# epd_driver.net
KiCad netlist of a schematic drawn in Altium Designer
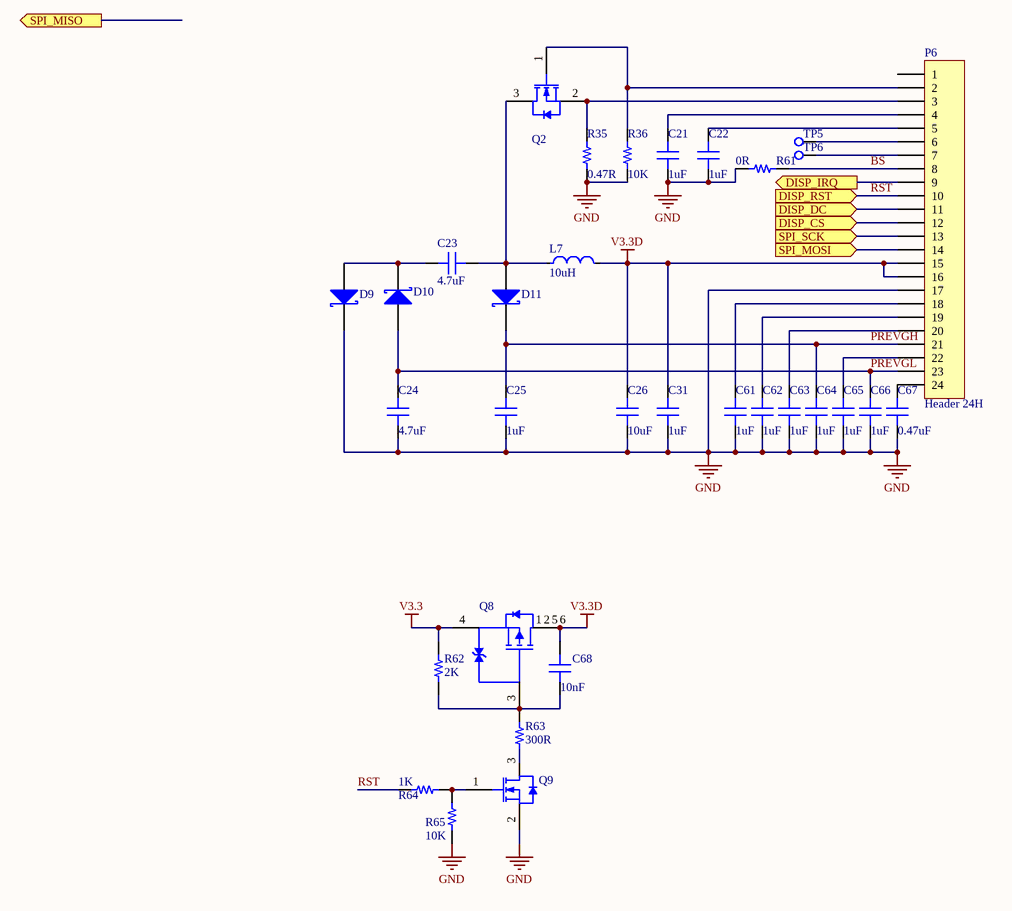
[diagram p0: epd_driver.SchDoc]

(export (version "E")
  (design (tool "Eeschema 10.0.6"))
  (components
    (comp (ref "C21")
      (value "1uF")
      (footprint "CAP 0603_1608")
      (description "SMT Capacitor")
      (fields (field (name "MF") "Murata") (field (name "MP") "GRT188R61H105KE13D"))
      (libsource (lib "Capacitor") (part "Capacitor"))
    )
    (comp (ref "C22")
      (value "1uF")
      (footprint "CAP 0603_1608")
      (description "SMT Capacitor")
      (fields (field (name "MF") "Murata") (field (name "MP") "GRT188R61H105KE13D"))
      (libsource (lib "Capacitor") (part "Capacitor"))
    )
    (comp (ref "C23")
      (value "4.7uF")
      (footprint "CAP 0603_1608")
      (description "SMT Capacitor")
      (fields (field (name "MF") "Murata") (field (name "MP") "GRM188C81E475KE11J"))
      (libsource (lib "Capacitor") (part "Capacitor"))
    )
    (comp (ref "C24")
      (value "4.7uF")
      (footprint "CAP 0603_1608")
      (description "SMT Capacitor")
      (fields (field (name "MF") "Murata") (field (name "MP") "GRM188C81E475KE11J"))
      (libsource (lib "Capacitor") (part "Capacitor"))
    )
    (comp (ref "C25")
      (value "1uF")
      (footprint "CAP 0603_1608")
      (description "SMT Capacitor")
      (fields (field (name "MF") "Murata") (field (name "MP") "GRT188R61H105KE13D"))
      (libsource (lib "Capacitor") (part "Capacitor"))
    )
    (comp (ref "C26")
      (value "10uF")
      (footprint "CAP 0603_1608")
      (description "SMT Capacitor")
      (fields (field (name "MF") "Murata") (field (name "MP") "GRM188R61C106MAALD"))
      (libsource (lib "Capacitor") (part "Capacitor"))
    )
    (comp (ref "C31")
      (value "1uF")
      (footprint "CAP 0603_1608")
      (description "SMT Capacitor")
      (fields (field (name "MF") "Murata") (field (name "MP") "GRT188R61H105KE13D"))
      (libsource (lib "Capacitor") (part "Capacitor"))
    )
    (comp (ref "C61")
      (value "1uF")
      (footprint "CAP 0603_1608")
      (description "SMT Capacitor")
      (fields (field (name "MF") "Murata") (field (name "MP") "GRT188R61H105KE13D"))
      (libsource (lib "Capacitor") (part "Capacitor"))
    )
    (comp (ref "C62")
      (value "1uF")
      (footprint "CAP 0603_1608")
      (description "SMT Capacitor")
      (fields (field (name "MF") "Murata") (field (name "MP") "GRT188R61H105KE13D"))
      (libsource (lib "Capacitor") (part "Capacitor"))
    )
    (comp (ref "C63")
      (value "1uF")
      (footprint "CAP 0603_1608")
      (description "SMT Capacitor")
      (fields (field (name "MF") "Murata") (field (name "MP") "GRT188R61H105KE13D"))
      (libsource (lib "Capacitor") (part "Capacitor"))
    )
    (comp (ref "C64")
      (value "1uF")
      (footprint "CAP 0603_1608")
      (description "SMT Capacitor")
      (fields (field (name "MF") "Murata") (field (name "MP") "GRT188R61H105KE13D"))
      (libsource (lib "Capacitor") (part "Capacitor"))
    )
    (comp (ref "C65")
      (value "1uF")
      (footprint "CAP 0603_1608")
      (description "SMT Capacitor")
      (fields (field (name "MF") "Murata") (field (name "MP") "GRT188R61H105KE13D"))
      (libsource (lib "Capacitor") (part "Capacitor"))
    )
    (comp (ref "C66")
      (value "1uF")
      (footprint "CAP 0603_1608")
      (description "SMT Capacitor")
      (fields (field (name "MF") "Murata") (field (name "MP") "GRT188R61H105KE13D"))
      (libsource (lib "Capacitor") (part "Capacitor"))
    )
    (comp (ref "C67")
      (value "0.47uF")
      (footprint "CAP 0603_1608")
      (description "SMT Capacitor")
      (fields (field (name "MF") "Samsung") (field (name "MP") "CL10B474KA8NFNC"))
      (libsource (lib "Capacitor") (part "Capacitor"))
    )
    (comp (ref "C68")
      (value "10nF")
      (footprint "CAP 0603_1608")
      (description "SMT Capacitor")
      (fields (field (name "MF") "Murata") (field (name "MP") "GRM1885C1E103JA01D"))
      (libsource (lib "Capacitor") (part "Capacitor"))
    )
    (comp (ref "D9")
      (value "*")
      (footprint "Rohm_TUMD2M_MFG")
      (fields (field (name "MF") "Toshiba") (field (name "MP") "CUHS20F30,H3F"))
      (libsource (lib "Diode") (part "Schottky Diode"))
    )
    (comp (ref "D10")
      (value "*")
      (footprint "Rohm_TUMD2M_MFG")
      (fields (field (name "MF") "Toshiba") (field (name "MP") "CUHS20F30,H3F"))
      (libsource (lib "Diode") (part "Schottky Diode"))
    )
    (comp (ref "D11")
      (value "*")
      (footprint "Rohm_TUMD2M_MFG")
      (fields (field (name "MF") "Toshiba") (field (name "MP") "CUHS20F30,H3F"))
      (libsource (lib "Diode") (part "Schottky Diode"))
    )
    (comp (ref "L7")
      (value "10uH")
      (footprint "IND 1008_2520")
      (description "Fixed Inductors 2.2uH 20% High Temp AEC-Q200")
      (fields (field (name "MF") "Murata") (field (name "MP") "DFE252012F-100M=P2"))
      (libsource (lib "Inductor") (part "Inductor_sm"))
    )
    (comp (ref "P6")
      (value "Header 24H")
      (footprint "Amphenol_FFC/FPC_24_0.5mm")
      (description "Header, 24-Pin, Right Angle")
      (fields
        (field (name "MF") "Amphenol")
        (field (name "MP") "10051922-2410EHLF")
        (field (name "PUBLISHER") "Altium Limited")
      )
      (libsource (lib "Connector") (part "Header 24H"))
    )
    (comp (ref "Q2")
      (value "N Mosfet")
      (footprint "ON SEMI SOT-23-3")
      (description "N-Channel Enhancement Mode MOS Transistor, 30 V, 0.85 A, 3-Pin SOT23, Tape and Reel")
      (fields (field (name "MF") "Diodes") (field (name "MP") "DMN2053U-7"))
      (libsource (lib "Mosfet") (part "Mosfet-N"))
    )
    (comp (ref "Q8")
      (value "P Mosfet")
      (footprint "Diodes_Inc._TSOT26_MFG")
      (description "P-Channel Enhancement Mode MOS Transistor, 3-Pin SOT23")
      (fields (field (name "MF") "Vishay") (field (name "MP") "SI3421DV-T1-GE3"))
      (libsource (lib "Mosfet") (part "Mosfet-P-6_ESD"))
    )
    (comp (ref "Q9")
      (value "N Mosfet")
      (footprint "ON SEMI SOT-23-3")
      (description "N-Channel Enhancement Mode MOS Transistor, 30 V, 0.85 A, 3-Pin SOT23, Tape and Reel")
      (fields (field (name "MF") "Diodes") (field (name "MP") "DMN2053U-7"))
      (libsource (lib "Mosfet") (part "Mosfet-N"))
    )
    (comp (ref "R35")
      (value "0.47R")
      (footprint "RES 0603_1608")
      (description "SMT Resistor")
      (fields (field (name "MF") "Panasonic") (field (name "MP") "ERJ-3RQFR47V"))
      (libsource (lib "Resistor") (part "Resistor"))
    )
    (comp (ref "R36")
      (value "10K")
      (footprint "RES 0603_1608")
      (description "SMT Resistor")
      (fields (field (name "MF") "YAGEO") (field (name "MP") "AC0603FR-0710KL"))
      (libsource (lib "Resistor") (part "Resistor"))
    )
    (comp (ref "R61")
      (value "0R")
      (footprint "RES 0603_1608")
      (description "SMT Resistor")
      (fields (field (name "MF") "YAGEO") (field (name "MP") "AC0603FR-070RL"))
      (libsource (lib "Resistor") (part "Resistor"))
    )
    (comp (ref "R62")
      (value "2K")
      (footprint "RES 0603_1608")
      (description "SMT Resistor")
      (fields (field (name "MF") "YAGEO") (field (name "MP") "AC0603FR-072KL"))
      (libsource (lib "Resistor") (part "Resistor"))
    )
    (comp (ref "R63")
      (value "300R")
      (footprint "RES 0603_1608")
      (description "SMT Resistor")
      (fields (field (name "MF") "YAGEO") (field (name "MP") "AC0603FR-07300RL"))
      (libsource (lib "Resistor") (part "Resistor"))
    )
    (comp (ref "R64")
      (value "1K")
      (footprint "RES 0603_1608")
      (description "SMT Resistor")
      (fields (field (name "MF") "YAGEO") (field (name "MP") "AC0603FR-071KL"))
      (libsource (lib "Resistor") (part "Resistor"))
    )
    (comp (ref "R65")
      (value "10K")
      (footprint "RES 0603_1608")
      (description "SMT Resistor")
      (fields (field (name "MF") "YAGEO") (field (name "MP") "AC0603FR-0710KL"))
      (libsource (lib "Resistor") (part "Resistor"))
    )
    (comp (ref "TP5")
      (value "Test Point")
      (footprint "TPSMD_S1")
      (libsource (lib "Passive") (part "Test Point"))
    )
    (comp (ref "TP6")
      (value "Test Point")
      (footprint "TPSMD_S1")
      (libsource (lib "Passive") (part "Test Point"))
    )
  )
  (nets
    (net (code "1") (name "/BS") (class "Default")
      (node (ref "P6") (pin "8") (pinfunction "8_8") (pintype "passive"))
      (node (ref "R61") (pin "1") (pinfunction "1_1") (pintype "passive"))
    )
    (net (code "2") (name "/DISP_CS") (class "Default")
      (node (ref "P6") (pin "12") (pinfunction "12_12") (pintype "passive"))
    )
    (net (code "3") (name "/DISP_DC") (class "Default")
      (node (ref "P6") (pin "11") (pinfunction "11_11") (pintype "passive"))
    )
    (net (code "4") (name "/DISP_IRQ") (class "Default")
      (node (ref "P6") (pin "9") (pinfunction "9_9") (pintype "passive"))
    )
    (net (code "5") (name "/PREVGH") (class "Default")
      (node (ref "C25") (pin "2") (pinfunction "2_2") (pintype "passive"))
      (node (ref "C64") (pin "2") (pinfunction "2_2") (pintype "passive"))
      (node (ref "D11") (pin "1") (pinfunction "K_1") (pintype "passive"))
      (node (ref "P6") (pin "21") (pinfunction "21_21") (pintype "passive"))
    )
    (net (code "6") (name "/PREVGL") (class "Default")
      (node (ref "C24") (pin "1") (pinfunction "1_1") (pintype "passive"))
      (node (ref "C66") (pin "2") (pinfunction "2_2") (pintype "passive"))
      (node (ref "D10") (pin "2") (pinfunction "A_2") (pintype "passive"))
      (node (ref "P6") (pin "23") (pinfunction "23_23") (pintype "passive"))
    )
    (net (code "7") (name "/RST") (class "Default")
      (node (ref "P6") (pin "10") (pinfunction "10_10") (pintype "passive"))
      (node (ref "R64") (pin "1") (pinfunction "1_1") (pintype "passive"))
    )
    (net (code "9") (name "/SPI_MOSI") (class "Default")
      (node (ref "P6") (pin "14") (pinfunction "14_14") (pintype "passive"))
    )
    (net (code "10") (name "/SPI_SCK") (class "Default")
      (node (ref "P6") (pin "13") (pinfunction "13_13") (pintype "passive"))
    )
    (net (code "11") (name "GND") (class "Default")
      (node (ref "C21") (pin "1") (pinfunction "1_1") (pintype "passive"))
      (node (ref "C22") (pin "1") (pinfunction "1_1") (pintype "passive"))
      (node (ref "C24") (pin "2") (pinfunction "2_2") (pintype "passive"))
      (node (ref "C25") (pin "1") (pinfunction "1_1") (pintype "passive"))
      (node (ref "C26") (pin "2") (pinfunction "2_2") (pintype "passive"))
      (node (ref "C31") (pin "1") (pinfunction "1_1") (pintype "passive"))
      (node (ref "C61") (pin "1") (pinfunction "1_1") (pintype "passive"))
      (node (ref "C62") (pin "1") (pinfunction "1_1") (pintype "passive"))
      (node (ref "C63") (pin "1") (pinfunction "1_1") (pintype "passive"))
      (node (ref "C64") (pin "1") (pinfunction "1_1") (pintype "passive"))
      (node (ref "C65") (pin "1") (pinfunction "1_1") (pintype "passive"))
      (node (ref "C66") (pin "1") (pinfunction "1_1") (pintype "passive"))
      (node (ref "C67") (pin "1") (pinfunction "1_1") (pintype "passive"))
      (node (ref "D9") (pin "1") (pinfunction "K_1") (pintype "passive"))
      (node (ref "P6") (pin "17") (pinfunction "17_17") (pintype "passive"))
      (node (ref "Q9") (pin "2") (pinfunction "S_2") (pintype "passive"))
      (node (ref "R35") (pin "1") (pinfunction "1_1") (pintype "passive"))
      (node (ref "R36") (pin "2") (pinfunction "2_2") (pintype "passive"))
      (node (ref "R61") (pin "2") (pinfunction "2_2") (pintype "passive"))
      (node (ref "R65") (pin "1") (pinfunction "1_1") (pintype "passive"))
    )
    (net (code "12") (name "Net-(C21-Pad2)") (class "Default")
      (node (ref "C21") (pin "2") (pinfunction "2_2") (pintype "passive"))
      (node (ref "P6") (pin "4") (pinfunction "4_4") (pintype "passive"))
    )
    (net (code "13") (name "Net-(C22-Pad2)") (class "Default")
      (node (ref "C22") (pin "2") (pinfunction "2_2") (pintype "passive"))
      (node (ref "P6") (pin "5") (pinfunction "5_5") (pintype "passive"))
    )
    (net (code "14") (name "Net-(C61-Pad2)") (class "Default")
      (node (ref "C61") (pin "2") (pinfunction "2_2") (pintype "passive"))
      (node (ref "P6") (pin "18") (pinfunction "18_18") (pintype "passive"))
    )
    (net (code "15") (name "Net-(C62-Pad2)") (class "Default")
      (node (ref "C62") (pin "2") (pinfunction "2_2") (pintype "passive"))
      (node (ref "P6") (pin "19") (pinfunction "19_19") (pintype "passive"))
    )
    (net (code "16") (name "Net-(C63-Pad2)") (class "Default")
      (node (ref "C63") (pin "2") (pinfunction "2_2") (pintype "passive"))
      (node (ref "P6") (pin "20") (pinfunction "20_20") (pintype "passive"))
    )
    (net (code "17") (name "Net-(C65-Pad2)") (class "Default")
      (node (ref "C65") (pin "2") (pinfunction "2_2") (pintype "passive"))
      (node (ref "P6") (pin "22") (pinfunction "22_22") (pintype "passive"))
    )
    (net (code "18") (name "Net-(C67-Pad2)") (class "Default")
      (node (ref "C67") (pin "2") (pinfunction "2_2") (pintype "passive"))
      (node (ref "P6") (pin "24") (pinfunction "24_24") (pintype "passive"))
    )
    (net (code "19") (name "Net-(D10-K)") (class "Default")
      (node (ref "C23") (pin "1") (pinfunction "1_1") (pintype "passive"))
      (node (ref "D10") (pin "1") (pinfunction "K_1") (pintype "passive"))
      (node (ref "D9") (pin "2") (pinfunction "A_2") (pintype "passive"))
    )
    (net (code "20") (name "Net-(D11-A)") (class "Default")
      (node (ref "C23") (pin "2") (pinfunction "2_2") (pintype "passive"))
      (node (ref "D11") (pin "2") (pinfunction "A_2") (pintype "passive"))
      (node (ref "L7") (pin "1") (pinfunction "1_1") (pintype "passive"))
      (node (ref "Q2") (pin "3") (pinfunction "D_3") (pintype "passive"))
    )
    (net (code "21") (name "Net-(Q2-G)") (class "Default")
      (node (ref "P6") (pin "2") (pinfunction "2_2") (pintype "passive"))
      (node (ref "Q2") (pin "1") (pinfunction "G_1") (pintype "passive"))
      (node (ref "R36") (pin "1") (pinfunction "1_1") (pintype "passive"))
    )
    (net (code "22") (name "Net-(Q2-S)") (class "Default")
      (node (ref "P6") (pin "3") (pinfunction "3_3") (pintype "passive"))
      (node (ref "Q2") (pin "2") (pinfunction "S_2") (pintype "passive"))
      (node (ref "R35") (pin "2") (pinfunction "2_2") (pintype "passive"))
    )
    (net (code "23") (name "Net-(Q8-G)") (class "Default")
      (node (ref "C68") (pin "2") (pinfunction "2_2") (pintype "passive"))
      (node (ref "Q8") (pin "3") (pinfunction "G_3") (pintype "passive"))
      (node (ref "R62") (pin "2") (pinfunction "2_2") (pintype "passive"))
      (node (ref "R63") (pin "2") (pinfunction "2_2") (pintype "passive"))
    )
    (net (code "24") (name "Net-(Q9-D)") (class "Default")
      (node (ref "Q9") (pin "3") (pinfunction "D_3") (pintype "passive"))
      (node (ref "R63") (pin "1") (pinfunction "1_1") (pintype "passive"))
    )
    (net (code "25") (name "Net-(Q9-G)") (class "Default")
      (node (ref "Q9") (pin "1") (pinfunction "G_1") (pintype "passive"))
      (node (ref "R64") (pin "2") (pinfunction "2_2") (pintype "passive"))
      (node (ref "R65") (pin "2") (pinfunction "2_2") (pintype "passive"))
    )
    (net (code "26") (name "Net-(TP5-TP)") (class "Default")
      (node (ref "P6") (pin "6") (pinfunction "6_6") (pintype "passive"))
      (node (ref "TP5") (pin "1") (pinfunction "TP_1") (pintype "passive"))
    )
    (net (code "27") (name "Net-(TP6-TP)") (class "Default")
      (node (ref "P6") (pin "7") (pinfunction "7_7") (pintype "passive"))
      (node (ref "TP6") (pin "1") (pinfunction "TP_1") (pintype "passive"))
    )
    (net (code "28") (name "V3.3") (class "Default")
      (node (ref "Q8") (pin "4") (pinfunction "S_4") (pintype "passive"))
      (node (ref "R62") (pin "1") (pinfunction "1_1") (pintype "passive"))
    )
    (net (code "29") (name "V3.3D") (class "Default")
      (node (ref "C26") (pin "1") (pinfunction "1_1") (pintype "passive"))
      (node (ref "C31") (pin "2") (pinfunction "2_2") (pintype "passive"))
      (node (ref "C68") (pin "1") (pinfunction "1_1") (pintype "passive"))
      (node (ref "L7") (pin "2") (pinfunction "2_2") (pintype "passive"))
      (node (ref "P6") (pin "15") (pinfunction "15_15") (pintype "passive"))
      (node (ref "P6") (pin "16") (pinfunction "16_16") (pintype "passive"))
      (node (ref "Q8") (pin "1") (pinfunction "D_1") (pintype "passive"))
      (node (ref "Q8") (pin "2") (pinfunction "D_2") (pintype "passive"))
      (node (ref "Q8") (pin "5") (pinfunction "D_5") (pintype "passive"))
      (node (ref "Q8") (pin "6") (pinfunction "D_6") (pintype "passive"))
    )
    (net (code "30") (name "unconnected-(P6-GND-Pad25)") (class "Default")
      (node (ref "P6") (pin "25") (pinfunction "GND_25") (pintype "passive"))
    )
    (net (code "31") (name "unconnected-(P6-GND-Pad26)") (class "Default")
      (node (ref "P6") (pin "26") (pinfunction "GND_26") (pintype "passive"))
    )
    (net (code "32") (name "unconnected-(P6-Pad1)") (class "Default")
      (node (ref "P6") (pin "1") (pinfunction "1_1") (pintype "passive"))
    )
  )
)
